# nanoTouch.net
KiCad netlist of a schematic drawn in EAGLE
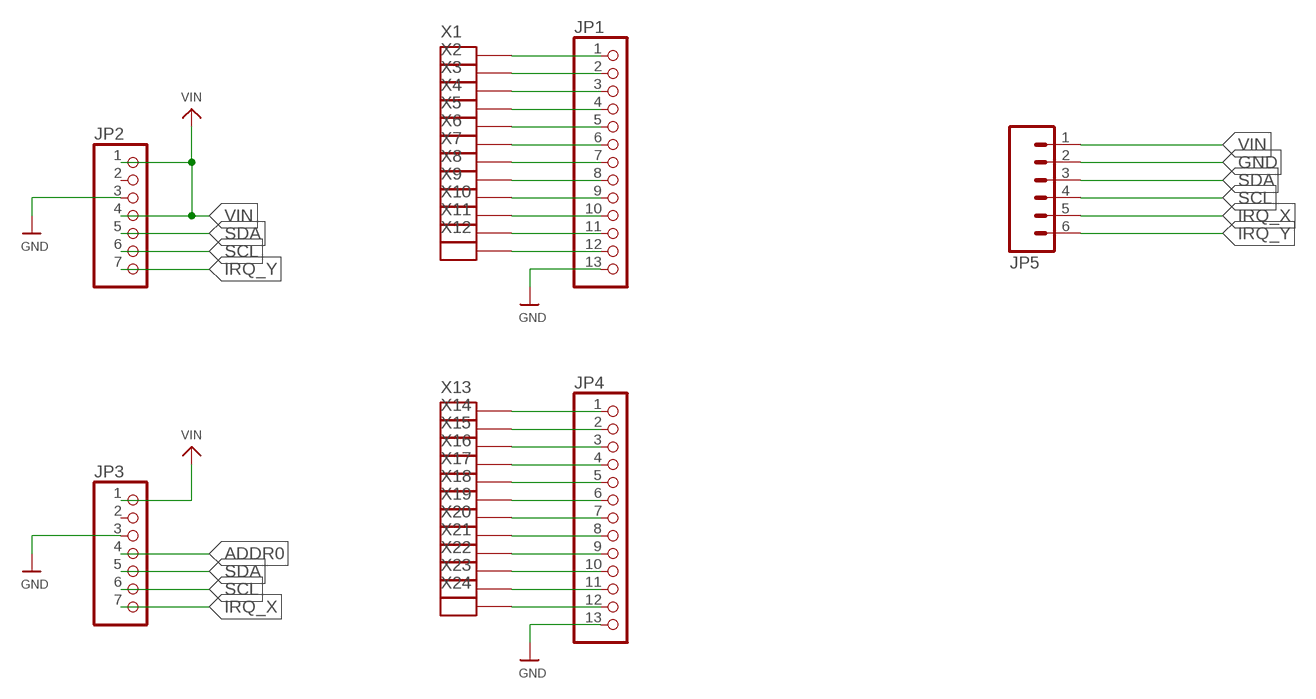
[diagram p0: schematic, sheet 1]

(export (version "E")
  (design (tool "Eeschema 10.0.6"))
  (components
    (comp (ref "JP1")
      (value "HEADER-1X13")
      (footprint "eagle-import:1X13_ROUND_70")
      (libsource (lib "eagle-import") (part "HEADER-1X13"))
    )
    (comp (ref "JP2")
      (value "HEADER-1X770MIL")
      (footprint "eagle-import:1X07_ROUND_70")
      (libsource (lib "eagle-import") (part "HEADER-1X770MIL"))
    )
    (comp (ref "JP3")
      (value "HEADER-1X770MIL")
      (footprint "eagle-import:1X07_ROUND_70")
      (libsource (lib "eagle-import") (part "HEADER-1X770MIL"))
    )
    (comp (ref "JP4")
      (value "HEADER-1X13")
      (footprint "eagle-import:1X13_ROUND_70")
      (libsource (lib "eagle-import") (part "HEADER-1X13"))
    )
    (comp (ref "JP5")
      (value "M06SILK_FEMALE_PTH")
      (footprint "eagle-import:1X06")
      (libsource (lib "eagle-import") (part "M06SILK_FEMALE_PTH"))
    )
    (comp (ref "X1")
      (value "PAD-2X2")
      (footprint "eagle-import:PAD2X2")
      (libsource (lib "eagle-import") (part "PAD-2X2"))
    )
    (comp (ref "X2")
      (value "PAD-2X2")
      (footprint "eagle-import:PAD2X2")
      (libsource (lib "eagle-import") (part "PAD-2X2"))
    )
    (comp (ref "X3")
      (value "PAD-2X2")
      (footprint "eagle-import:PAD2X2")
      (libsource (lib "eagle-import") (part "PAD-2X2"))
    )
    (comp (ref "X4")
      (value "PAD-2X2")
      (footprint "eagle-import:PAD2X2")
      (libsource (lib "eagle-import") (part "PAD-2X2"))
    )
    (comp (ref "X5")
      (value "PAD-2X2")
      (footprint "eagle-import:PAD2X2")
      (libsource (lib "eagle-import") (part "PAD-2X2"))
    )
    (comp (ref "X6")
      (value "PAD-2X2")
      (footprint "eagle-import:PAD2X2")
      (libsource (lib "eagle-import") (part "PAD-2X2"))
    )
    (comp (ref "X7")
      (value "PAD-2X2")
      (footprint "eagle-import:PAD2X2")
      (libsource (lib "eagle-import") (part "PAD-2X2"))
    )
    (comp (ref "X8")
      (value "PAD-2X2")
      (footprint "eagle-import:PAD2X2")
      (libsource (lib "eagle-import") (part "PAD-2X2"))
    )
    (comp (ref "X9")
      (value "PAD-2X2")
      (footprint "eagle-import:PAD2X2")
      (libsource (lib "eagle-import") (part "PAD-2X2"))
    )
    (comp (ref "X10")
      (value "PAD-2X2")
      (footprint "eagle-import:PAD2X2")
      (libsource (lib "eagle-import") (part "PAD-2X2"))
    )
    (comp (ref "X11")
      (value "PAD-2X2")
      (footprint "eagle-import:PAD2X2")
      (libsource (lib "eagle-import") (part "PAD-2X2"))
    )
    (comp (ref "X12")
      (value "PAD-2X2")
      (footprint "eagle-import:PAD2X2")
      (libsource (lib "eagle-import") (part "PAD-2X2"))
    )
    (comp (ref "X13")
      (value "PAD-2X2")
      (footprint "eagle-import:PAD2X2")
      (libsource (lib "eagle-import") (part "PAD-2X2"))
    )
    (comp (ref "X14")
      (value "PAD-2X2")
      (footprint "eagle-import:PAD2X2")
      (libsource (lib "eagle-import") (part "PAD-2X2"))
    )
    (comp (ref "X15")
      (value "PAD-2X2")
      (footprint "eagle-import:PAD2X2")
      (libsource (lib "eagle-import") (part "PAD-2X2"))
    )
    (comp (ref "X16")
      (value "PAD-2X2")
      (footprint "eagle-import:PAD2X2")
      (libsource (lib "eagle-import") (part "PAD-2X2"))
    )
    (comp (ref "X17")
      (value "PAD-2X2")
      (footprint "eagle-import:PAD2X2")
      (libsource (lib "eagle-import") (part "PAD-2X2"))
    )
    (comp (ref "X18")
      (value "PAD-2X2")
      (footprint "eagle-import:PAD2X2")
      (libsource (lib "eagle-import") (part "PAD-2X2"))
    )
    (comp (ref "X19")
      (value "PAD-2X2")
      (footprint "eagle-import:PAD2X2")
      (libsource (lib "eagle-import") (part "PAD-2X2"))
    )
    (comp (ref "X20")
      (value "PAD-2X2")
      (footprint "eagle-import:PAD2X2")
      (libsource (lib "eagle-import") (part "PAD-2X2"))
    )
    (comp (ref "X21")
      (value "PAD-2X2")
      (footprint "eagle-import:PAD2X2")
      (libsource (lib "eagle-import") (part "PAD-2X2"))
    )
    (comp (ref "X22")
      (value "PAD-2X2")
      (footprint "eagle-import:PAD2X2")
      (libsource (lib "eagle-import") (part "PAD-2X2"))
    )
    (comp (ref "X23")
      (value "PAD-2X2")
      (footprint "eagle-import:PAD2X2")
      (libsource (lib "eagle-import") (part "PAD-2X2"))
    )
    (comp (ref "X24")
      (value "PAD-2X2")
      (footprint "eagle-import:PAD2X2")
      (libsource (lib "eagle-import") (part "PAD-2X2"))
    )
  )
  (nets
    (net (code "1") (name "ADDR0") (class "Default")
      (node (ref "JP3") (pin "4") (pinfunction "4_4") (pintype "passive"))
    )
    (net (code "2") (name "GND") (class "Default")
      (node (ref "JP1") (pin "13") (pinfunction "13_13") (pintype "passive"))
      (node (ref "JP2") (pin "3") (pinfunction "3_3") (pintype "passive"))
      (node (ref "JP3") (pin "3") (pinfunction "3_3") (pintype "passive"))
      (node (ref "JP4") (pin "13") (pinfunction "13_13") (pintype "passive"))
      (node (ref "JP5") (pin "2") (pinfunction "2_2") (pintype "passive"))
    )
    (net (code "3") (name "IRQ_X") (class "Default")
      (node (ref "JP3") (pin "7") (pinfunction "7_7") (pintype "passive"))
      (node (ref "JP5") (pin "5") (pinfunction "5_5") (pintype "passive"))
    )
    (net (code "4") (name "IRQ_Y") (class "Default")
      (node (ref "JP2") (pin "7") (pinfunction "7_7") (pintype "passive"))
      (node (ref "JP5") (pin "6") (pinfunction "6_6") (pintype "passive"))
    )
    (net (code "5") (name "Net-(JP1-Pad1)") (class "Default")
      (node (ref "JP1") (pin "1") (pinfunction "1_1") (pintype "passive"))
      (node (ref "X1") (pin "P$1") (pinfunction "P$1_P$1") (pintype "bidirectional"))
    )
    (net (code "6") (name "Net-(JP1-Pad2)") (class "Default")
      (node (ref "JP1") (pin "2") (pinfunction "2_2") (pintype "passive"))
      (node (ref "X2") (pin "P$1") (pinfunction "P$1_P$1") (pintype "bidirectional"))
    )
    (net (code "7") (name "Net-(JP1-Pad3)") (class "Default")
      (node (ref "JP1") (pin "3") (pinfunction "3_3") (pintype "passive"))
      (node (ref "X3") (pin "P$1") (pinfunction "P$1_P$1") (pintype "bidirectional"))
    )
    (net (code "8") (name "Net-(JP1-Pad4)") (class "Default")
      (node (ref "JP1") (pin "4") (pinfunction "4_4") (pintype "passive"))
      (node (ref "X4") (pin "P$1") (pinfunction "P$1_P$1") (pintype "bidirectional"))
    )
    (net (code "9") (name "Net-(JP1-Pad5)") (class "Default")
      (node (ref "JP1") (pin "5") (pinfunction "5_5") (pintype "passive"))
      (node (ref "X5") (pin "P$1") (pinfunction "P$1_P$1") (pintype "bidirectional"))
    )
    (net (code "10") (name "Net-(JP1-Pad6)") (class "Default")
      (node (ref "JP1") (pin "6") (pinfunction "6_6") (pintype "passive"))
      (node (ref "X6") (pin "P$1") (pinfunction "P$1_P$1") (pintype "bidirectional"))
    )
    (net (code "11") (name "Net-(JP1-Pad7)") (class "Default")
      (node (ref "JP1") (pin "7") (pinfunction "7_7") (pintype "passive"))
      (node (ref "X7") (pin "P$1") (pinfunction "P$1_P$1") (pintype "bidirectional"))
    )
    (net (code "12") (name "Net-(JP1-Pad8)") (class "Default")
      (node (ref "JP1") (pin "8") (pinfunction "8_8") (pintype "passive"))
      (node (ref "X8") (pin "P$1") (pinfunction "P$1_P$1") (pintype "bidirectional"))
    )
    (net (code "13") (name "Net-(JP1-Pad9)") (class "Default")
      (node (ref "JP1") (pin "9") (pinfunction "9_9") (pintype "passive"))
      (node (ref "X9") (pin "P$1") (pinfunction "P$1_P$1") (pintype "bidirectional"))
    )
    (net (code "14") (name "Net-(JP1-Pad10)") (class "Default")
      (node (ref "JP1") (pin "10") (pinfunction "10_10") (pintype "passive"))
      (node (ref "X10") (pin "P$1") (pinfunction "P$1_P$1") (pintype "bidirectional"))
    )
    (net (code "15") (name "Net-(JP1-Pad11)") (class "Default")
      (node (ref "JP1") (pin "11") (pinfunction "11_11") (pintype "passive"))
      (node (ref "X11") (pin "P$1") (pinfunction "P$1_P$1") (pintype "bidirectional"))
    )
    (net (code "16") (name "Net-(JP1-Pad12)") (class "Default")
      (node (ref "JP1") (pin "12") (pinfunction "12_12") (pintype "passive"))
      (node (ref "X12") (pin "P$1") (pinfunction "P$1_P$1") (pintype "bidirectional"))
    )
    (net (code "17") (name "Net-(JP4-Pad1)") (class "Default")
      (node (ref "JP4") (pin "1") (pinfunction "1_1") (pintype "passive"))
      (node (ref "X13") (pin "P$1") (pinfunction "P$1_P$1") (pintype "bidirectional"))
    )
    (net (code "18") (name "Net-(JP4-Pad2)") (class "Default")
      (node (ref "JP4") (pin "2") (pinfunction "2_2") (pintype "passive"))
      (node (ref "X14") (pin "P$1") (pinfunction "P$1_P$1") (pintype "bidirectional"))
    )
    (net (code "19") (name "Net-(JP4-Pad3)") (class "Default")
      (node (ref "JP4") (pin "3") (pinfunction "3_3") (pintype "passive"))
      (node (ref "X15") (pin "P$1") (pinfunction "P$1_P$1") (pintype "bidirectional"))
    )
    (net (code "20") (name "Net-(JP4-Pad4)") (class "Default")
      (node (ref "JP4") (pin "4") (pinfunction "4_4") (pintype "passive"))
      (node (ref "X16") (pin "P$1") (pinfunction "P$1_P$1") (pintype "bidirectional"))
    )
    (net (code "21") (name "Net-(JP4-Pad5)") (class "Default")
      (node (ref "JP4") (pin "5") (pinfunction "5_5") (pintype "passive"))
      (node (ref "X17") (pin "P$1") (pinfunction "P$1_P$1") (pintype "bidirectional"))
    )
    (net (code "22") (name "Net-(JP4-Pad6)") (class "Default")
      (node (ref "JP4") (pin "6") (pinfunction "6_6") (pintype "passive"))
      (node (ref "X18") (pin "P$1") (pinfunction "P$1_P$1") (pintype "bidirectional"))
    )
    (net (code "23") (name "Net-(JP4-Pad7)") (class "Default")
      (node (ref "JP4") (pin "7") (pinfunction "7_7") (pintype "passive"))
      (node (ref "X19") (pin "P$1") (pinfunction "P$1_P$1") (pintype "bidirectional"))
    )
    (net (code "24") (name "Net-(JP4-Pad8)") (class "Default")
      (node (ref "JP4") (pin "8") (pinfunction "8_8") (pintype "passive"))
      (node (ref "X20") (pin "P$1") (pinfunction "P$1_P$1") (pintype "bidirectional"))
    )
    (net (code "25") (name "Net-(JP4-Pad9)") (class "Default")
      (node (ref "JP4") (pin "9") (pinfunction "9_9") (pintype "passive"))
      (node (ref "X21") (pin "P$1") (pinfunction "P$1_P$1") (pintype "bidirectional"))
    )
    (net (code "26") (name "Net-(JP4-Pad10)") (class "Default")
      (node (ref "JP4") (pin "10") (pinfunction "10_10") (pintype "passive"))
      (node (ref "X22") (pin "P$1") (pinfunction "P$1_P$1") (pintype "bidirectional"))
    )
    (net (code "27") (name "Net-(JP4-Pad11)") (class "Default")
      (node (ref "JP4") (pin "11") (pinfunction "11_11") (pintype "passive"))
      (node (ref "X23") (pin "P$1") (pinfunction "P$1_P$1") (pintype "bidirectional"))
    )
    (net (code "28") (name "Net-(JP4-Pad12)") (class "Default")
      (node (ref "JP4") (pin "12") (pinfunction "12_12") (pintype "passive"))
      (node (ref "X24") (pin "P$1") (pinfunction "P$1_P$1") (pintype "bidirectional"))
    )
    (net (code "29") (name "SCL") (class "Default")
      (node (ref "JP2") (pin "6") (pinfunction "6_6") (pintype "passive"))
      (node (ref "JP3") (pin "6") (pinfunction "6_6") (pintype "passive"))
      (node (ref "JP5") (pin "4") (pinfunction "4_4") (pintype "passive"))
    )
    (net (code "30") (name "SDA") (class "Default")
      (node (ref "JP2") (pin "5") (pinfunction "5_5") (pintype "passive"))
      (node (ref "JP3") (pin "5") (pinfunction "5_5") (pintype "passive"))
      (node (ref "JP5") (pin "3") (pinfunction "3_3") (pintype "passive"))
    )
    (net (code "31") (name "VIN") (class "Default")
      (node (ref "JP2") (pin "1") (pinfunction "1_1") (pintype "passive"))
      (node (ref "JP2") (pin "4") (pinfunction "4_4") (pintype "passive"))
      (node (ref "JP3") (pin "1") (pinfunction "1_1") (pintype "passive"))
      (node (ref "JP5") (pin "1") (pinfunction "1_1") (pintype "passive"))
    )
    (net (code "32") (name "unconnected-(JP2-Pad2)") (class "Default")
      (node (ref "JP2") (pin "2") (pinfunction "2_2") (pintype "passive"))
    )
    (net (code "33") (name "unconnected-(JP3-Pad2)") (class "Default")
      (node (ref "JP3") (pin "2") (pinfunction "2_2") (pintype "passive"))
    )
  )
)
